# LCD.net
KiCad netlist of a schematic drawn in Altium Designer
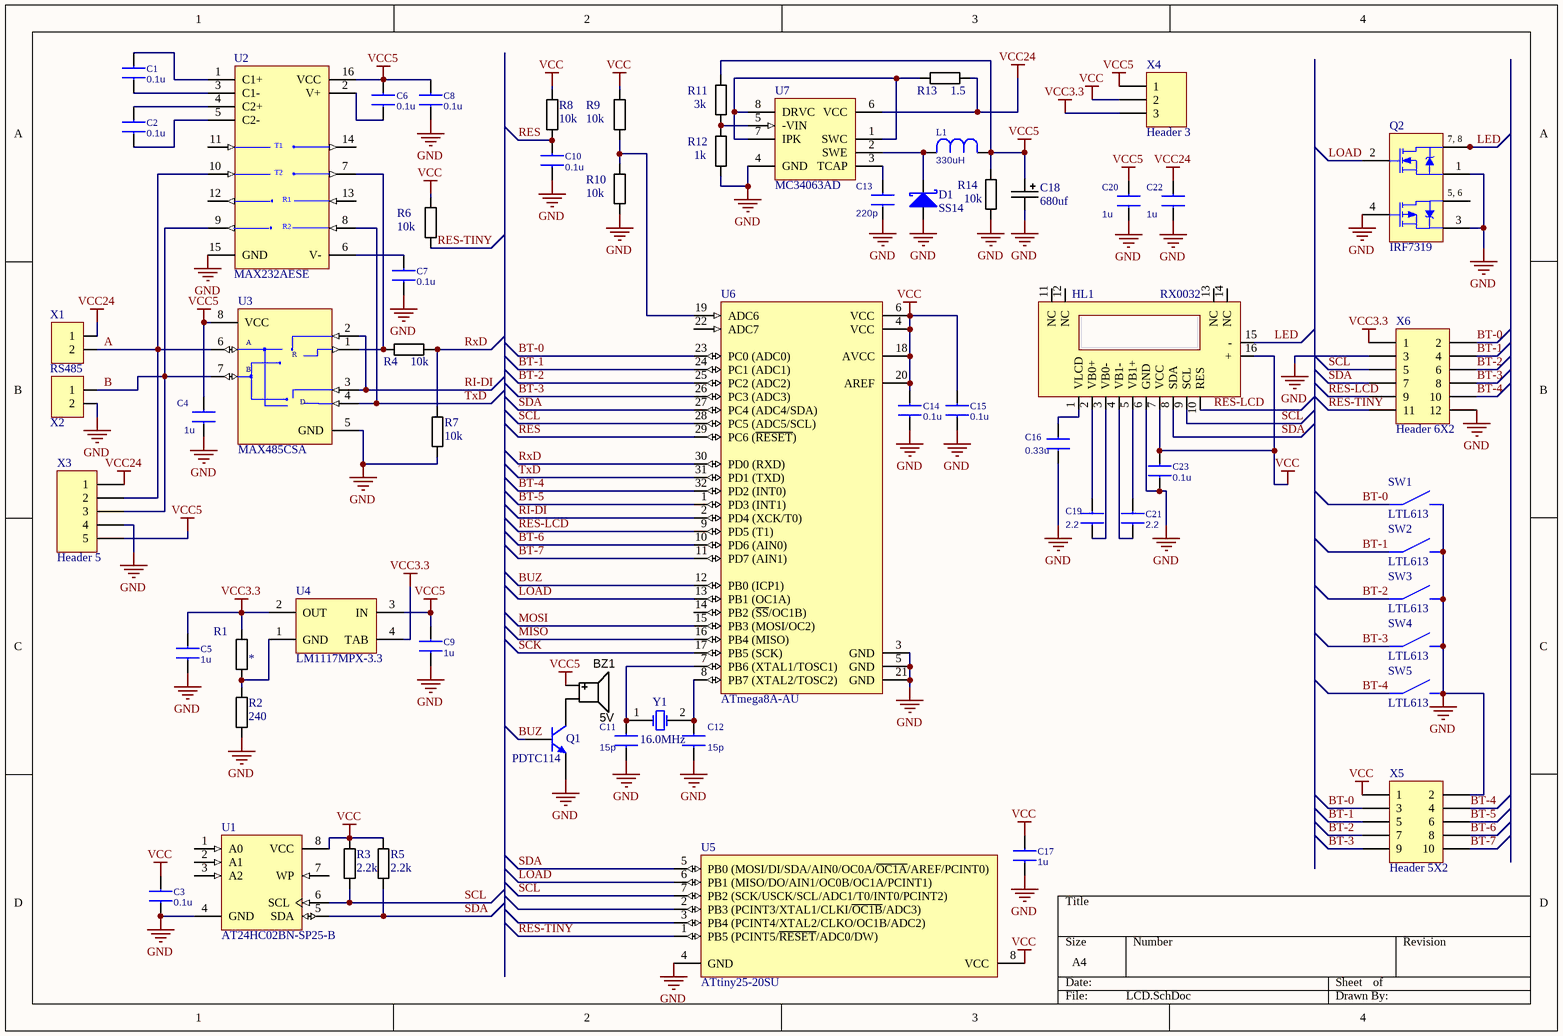
[diagram p0: LCD.SchDoc]

(export (version "E")
  (design (tool "Eeschema 10.0.6"))
  (components
    (comp (ref "BZ1")
      (value "Alternate part: 3100-932")
      (footprint "PBL - THD Packages:BUZZER_12.0X8.5MM")
      (description "Speaker, Magnetic Transducer")
      (fields (field (name "MANUFACTURER PART NUMBER 1") "5V"))
      (libsource (lib "PBL - Electromechanical") (part "BZ_12x8.5x6.5_2kHz"))
    )
    (comp (ref "C1")
      (value "0.1u")
      (footprint "C_0805")
      (description "Capacitor")
      (libsource (lib "AX_Altium_v2.3") (part "C0805"))
    )
    (comp (ref "C2")
      (value "0.1u")
      (footprint "C_0805")
      (description "Capacitor")
      (libsource (lib "AX_Altium_v2.3") (part "C0805"))
    )
    (comp (ref "C3")
      (value "0.1u")
      (footprint "C_0805")
      (description "Capacitor")
      (libsource (lib "AX_Altium_v2.3") (part "C0805"))
    )
    (comp (ref "C4")
      (value "1u")
      (footprint "C_0805")
      (description "Capacitor")
      (libsource (lib "AX_Altium_v2.3") (part "C0805"))
    )
    (comp (ref "C5")
      (value "1u")
      (footprint "C_0805")
      (description "Capacitor")
      (libsource (lib "AX_Altium_v2.3") (part "C0805"))
    )
    (comp (ref "C6")
      (value "0.1u")
      (footprint "C_0805")
      (description "Capacitor")
      (libsource (lib "AX_Altium_v2.3") (part "C0805"))
    )
    (comp (ref "C7")
      (value "0.1u")
      (footprint "C_0805")
      (description "Capacitor")
      (libsource (lib "AX_Altium_v2.3") (part "C0805"))
    )
    (comp (ref "C8")
      (value "0.1u")
      (footprint "C_0805")
      (description "Capacitor")
      (libsource (lib "AX_Altium_v2.3") (part "C0805"))
    )
    (comp (ref "C9")
      (value "1u")
      (footprint "C_0805")
      (description "Capacitor")
      (libsource (lib "AX_Altium_v2.3") (part "C0805"))
    )
    (comp (ref "C10")
      (value "0.1u")
      (footprint "C_0805")
      (description "Capacitor")
      (libsource (lib "AX_Altium_v2.3") (part "C0805"))
    )
    (comp (ref "C11")
      (value "15p")
      (footprint "C_0603")
      (description "Capacitor")
      (libsource (lib "AX_Altium_v2.3") (part "C0603"))
    )
    (comp (ref "C12")
      (value "15p")
      (footprint "C_0603")
      (description "Capacitor")
      (libsource (lib "AX_Altium_v2.3") (part "C0603"))
    )
    (comp (ref "C13")
      (value "220p")
      (footprint "C_0805")
      (description "Capacitor")
      (libsource (lib "AX_Altium_v2.3") (part "C0805"))
    )
    (comp (ref "C14")
      (value "0.1u")
      (footprint "C_0805")
      (description "Capacitor")
      (libsource (lib "AX_Altium_v2.3") (part "C0805"))
    )
    (comp (ref "C15")
      (value "0.1u")
      (footprint "C_0805")
      (description "Capacitor")
      (libsource (lib "AX_Altium_v2.3") (part "C0805"))
    )
    (comp (ref "C16")
      (value "0.33u")
      (footprint "C_0805")
      (description "Capacitor")
      (libsource (lib "AX_Altium_v2.3") (part "C0805"))
    )
    (comp (ref "C17")
      (value "1u")
      (footprint "C_0805")
      (description "Capacitor")
      (libsource (lib "AX_Altium_v2.3") (part "C0805"))
    )
    (comp (ref "C18")
      (value "680uf")
      (footprint "Cap-Elec-8x9pcb:PCBComponent_1")
      (fields (field (name "Comment") "Component_1"))
      (libsource (lib "Cap-Elec-8x9") (part "Component_1"))
    )
    (comp (ref "C19")
      (value "2.2")
      (footprint "C_1206")
      (description "Capacitor")
      (libsource (lib "AX_Altium_v2.3") (part "C1206"))
    )
    (comp (ref "C20")
      (value "1u")
      (footprint "C_0805")
      (description "Capacitor")
      (libsource (lib "AX_Altium_v2.3") (part "C0805"))
    )
    (comp (ref "C21")
      (value "2.2")
      (footprint "C_1206")
      (description "Capacitor")
      (libsource (lib "AX_Altium_v2.3") (part "C1206"))
    )
    (comp (ref "C22")
      (value "1u")
      (footprint "C_0805")
      (description "Capacitor")
      (libsource (lib "AX_Altium_v2.3") (part "C0805"))
    )
    (comp (ref "C23")
      (value "0.1u")
      (footprint "C_0805")
      (description "Capacitor")
      (libsource (lib "AX_Altium_v2.3") (part "C0805"))
    )
    (comp (ref "D1")
      (value "SS14")
      (footprint "DO-214AC")
      (description "Schottky Diode")
      (libsource (lib "AX_Altium_v2.3") (part "DS_DO-214"))
    )
    (comp (ref "HL1") (value "RX0032") (footprint "RX0032") (libsource (lib "RX0032") (part "RX0032")))
    (comp (ref "L1")
      (value "330uH")
      (footprint "CDRH74")
      (description "Inductor")
      (libsource (lib "AX_Altium_v2.3") (part "L_CDRH74"))
    )
    (comp (ref "Q1")
      (value "PDTC114")
      (footprint "SOT-23B_N")
      (description "NPN Bipolar Transistor")
      (fields (field (name "PUBLISHER") "Altium Limited"))
      (libsource (lib "Miscellaneous Devices") (part "QNPN"))
    )
    (comp (ref "Q2")
      (value "IRF7319")
      (footprint "SO-8")
      (description "HEXFET Power MOSFET")
      (fields (field (name "PUBLISHER") "Altium Limited"))
      (libsource (lib "AX_Altium_v2.3") (part "IRF7319"))
    )
    (comp (ref "R1") (value "*") (footprint "Resistor 0805") (libsource (lib "Maks_lib") (part "Resistor")))
    (comp (ref "R2") (value "240") (footprint "Resistor 0805") (libsource (lib "Maks_lib") (part "Resistor")))
    (comp (ref "R3")
      (value "2.2k")
      (footprint "Resistor 0603")
      (fields (field (name "Comment") "3k"))
      (libsource (lib "Maks_lib") (part "Resistor"))
    )
    (comp (ref "R4")
      (value "10k")
      (footprint "Resistor 0603")
      (fields (field (name "Comment") "3k"))
      (libsource (lib "Maks_lib") (part "Resistor"))
    )
    (comp (ref "R5")
      (value "2.2k")
      (footprint "Resistor 0603")
      (fields (field (name "Comment") "3k"))
      (libsource (lib "Maks_lib") (part "Resistor"))
    )
    (comp (ref "R6")
      (value "10k")
      (footprint "Resistor 0603")
      (fields (field (name "Comment") "3k"))
      (libsource (lib "Maks_lib") (part "Resistor"))
    )
    (comp (ref "R7")
      (value "10k")
      (footprint "Resistor 0603")
      (fields (field (name "Comment") "3k"))
      (libsource (lib "Maks_lib") (part "Resistor"))
    )
    (comp (ref "R8")
      (value "10k")
      (footprint "Resistor 0603")
      (fields (field (name "Comment") "3k"))
      (libsource (lib "Maks_lib") (part "Resistor"))
    )
    (comp (ref "R9")
      (value "10k")
      (footprint "Resistor 0603")
      (fields (field (name "Comment") "3k"))
      (libsource (lib "Maks_lib") (part "Resistor"))
    )
    (comp (ref "R10")
      (value "10k")
      (footprint "Resistor 0603")
      (fields (field (name "Comment") "3k"))
      (libsource (lib "Maks_lib") (part "Resistor"))
    )
    (comp (ref "R11") (value "3k") (footprint "Resistor 0603") (libsource (lib "Maks_lib") (part "Resistor")))
    (comp (ref "R12") (value "1k") (footprint "Resistor 0603") (libsource (lib "Maks_lib") (part "Resistor")))
    (comp (ref "R13")
      (value "1.5")
      (footprint "Resistor 1206")
      (fields (field (name "Comment") "3k"))
      (libsource (lib "Maks_lib") (part "Resistor"))
    )
    (comp (ref "R14")
      (value "10k")
      (footprint "Resistor 0603")
      (fields (field (name "Comment") "3k"))
      (libsource (lib "Maks_lib") (part "Resistor"))
    )
    (comp (ref "SW1")
      (value "LTL613")
      (footprint "LTL613")
      (description "Tact button switch")
      (libsource (lib "AX_Altium_v2.3") (part "Button_tact"))
    )
    (comp (ref "SW2")
      (value "LTL613")
      (footprint "LTL613")
      (description "Tact button switch")
      (libsource (lib "AX_Altium_v2.3") (part "Button_tact"))
    )
    (comp (ref "SW3")
      (value "LTL613")
      (footprint "LTL613")
      (description "Tact button switch")
      (libsource (lib "AX_Altium_v2.3") (part "Button_tact"))
    )
    (comp (ref "SW4")
      (value "LTL613")
      (footprint "LTL613")
      (description "Tact button switch")
      (libsource (lib "AX_Altium_v2.3") (part "Button_tact"))
    )
    (comp (ref "SW5")
      (value "LTL613")
      (footprint "LTL613")
      (description "Tact button switch")
      (libsource (lib "AX_Altium_v2.3") (part "Button_tact"))
    )
    (comp (ref "U1")
      (value "AT24HC02BN-SP25-B")
      (footprint "8S1_N")
      (fields (field (name "PUBLISHER") "Altium Limited"))
      (libsource (lib "Atmel Memory Serial EEPROM") (part "AT24HC02BN-SP25-B"))
    )
    (comp (ref "U2")
      (value "MAX232AESE")
      (footprint "NSO16_N")
      (description "+5V-Powered, Multichannel RS-232 Driver/Receiver")
      (fields (field (name "PUBLISHER") "Altium Limited"))
      (libsource (lib "Maxim Communication Transceiver") (part "MAX232AESE"))
    )
    (comp (ref "U3")
      (value "MAX485CSA")
      (footprint "NSO8_N")
      (description "Low-Power, Slew-Rate-Limited RS-485/RS-422 Transceiver")
      (fields (field (name "PUBLISHER") "Altium Limited"))
      (libsource (lib "Maxim Communication Transceiver") (part "MAX485CSA"))
    )
    (comp (ref "U4")
      (value "LM1117MPX-3.3")
      (footprint "MP04A_N")
      (description "800mA Low-Dropout Linear Regulator, 4-pin SOT-223")
      (fields
        (field (name "MANUFACTURER") "National Semiconductor")
        (field (name "PUBLISHER") "Altium Limited")
      )
      (libsource (lib "NSC LDO") (part "LM1117MPX-3.3"))
    )
    (comp (ref "U5")
      (value "ATtiny25-20SU")
      (footprint "8S2_N")
      (fields (field (name "PUBLISHER") "Altium Limited"))
      (libsource (lib "Atmel Microcontroller 8-Bit tinyAVR") (part "ATtiny25-20SU"))
    )
    (comp (ref "U6")
      (value "ATmega8A-AU")
      (footprint "32A_N")
      (fields (field (name "PUBLISHER") "Altium Limited"))
      (libsource (lib "Atmel Microcontroller 8-Bit megaAVR") (part "ATmega8A-AU"))
    )
    (comp (ref "U7")
      (value "MC34063AD")
      (footprint "751-02_N")
      (description "DC-to-DC Converter Control Circuit")
      (fields (field (name "PUBLISHER") "Altium Limited"))
      (libsource (lib "Motorola Power Mgt DC-DC Converter") (part "MC34063AD"))
    )
    (comp (ref "X1")
      (value "DG-2P-35")
      (footprint "DG-2P-35")
      (libsource (lib "Degson-uni-2P-35") (part "DG-2P-35"))
    )
    (comp (ref "X2")
      (value "DG-2P-35")
      (footprint "DG-2P-35")
      (fields (field (name "FOR") "RS485"))
      (libsource (lib "Degson-uni-2P-35") (part "DG-2P-35"))
    )
    (comp (ref "X3")
      (value "Header 5")
      (footprint "HDR1X5")
      (description "Header, 5-Pin")
      (fields (field (name "PUBLISHER") "Altium Limited"))
      (libsource (lib "Miscellaneous Connectors") (part "Header 5"))
    )
    (comp (ref "X4")
      (value "Header 3")
      (footprint "HDR1X3")
      (description "Header, 3-Pin")
      (fields (field (name "PUBLISHER") "Altium Limited"))
      (libsource (lib "Miscellaneous Connectors") (part "Header 3"))
    )
    (comp (ref "X5")
      (value "Header 5X2")
      (footprint "HDR2X5")
      (description "Header, 5-Pin, Dual row")
      (fields (field (name "PUBLISHER") "Altium Limited"))
      (libsource (lib "Miscellaneous Connectors") (part "Header 5X2"))
    )
    (comp (ref "X6")
      (value "Header 6X2")
      (footprint "HDR2X6")
      (description "Header, 6-Pin, Dual row")
      (fields (field (name "PUBLISHER") "Altium Limited"))
      (libsource (lib "Miscellaneous Connectors") (part "Header 6X2"))
    )
    (comp (ref "Y1")
      (value "16.0MHz")
      (footprint "HC49/4H_SMX")
      (description "Surface Mount Quartz Crystal")
      (fields (field (name "Comment") "HC49/4H_SMX") (field (name "PUBLISHER") "Altium Limited"))
      (libsource (lib "C-MAC Crystal Oscillator") (part "HC49/4H_SMX"))
    )
  )
  (nets
    (net (code "1") (name "/A") (class "Default")
      (node (ref "U2") (pin "10") (pinfunction "T2IN_10") (pintype "input"))
      (node (ref "U3") (pin "6") (pinfunction "A_6") (pintype "bidirectional"))
      (node (ref "X1") (pin "2") (pinfunction "2_2") (pintype "passive"))
      (node (ref "X3") (pin "2") (pinfunction "2_2") (pintype "passive"))
    )
    (net (code "2") (name "/B") (class "Default")
      (node (ref "U2") (pin "9") (pinfunction "R2OUT_9") (pintype "output"))
      (node (ref "U3") (pin "7") (pinfunction "B_7") (pintype "bidirectional"))
      (node (ref "X2") (pin "1") (pinfunction "1_1") (pintype "passive"))
      (node (ref "X3") (pin "3") (pinfunction "3_3") (pintype "passive"))
    )
    (net (code "3") (name "/BT-0") (class "Default")
      (node (ref "SW1") (pin "0") (pinfunction "0_0") (pintype "passive"))
      (node (ref "U6") (pin "23") (pinfunction "PC0_(ADC0)_23") (pintype "bidirectional"))
      (node (ref "X5") (pin "3") (pinfunction "3_3") (pintype "passive"))
      (node (ref "X6") (pin "2") (pinfunction "2_2") (pintype "passive"))
    )
    (net (code "4") (name "/BT-1") (class "Default")
      (node (ref "SW2") (pin "0") (pinfunction "0_0") (pintype "passive"))
      (node (ref "U6") (pin "24") (pinfunction "PC1_(ADC1)_24") (pintype "bidirectional"))
      (node (ref "X5") (pin "5") (pinfunction "5_5") (pintype "passive"))
      (node (ref "X6") (pin "4") (pinfunction "4_4") (pintype "passive"))
    )
    (net (code "5") (name "/BT-2") (class "Default")
      (node (ref "SW3") (pin "0") (pinfunction "0_0") (pintype "passive"))
      (node (ref "U6") (pin "25") (pinfunction "PC2_(ADC2)_25") (pintype "bidirectional"))
      (node (ref "X5") (pin "7") (pinfunction "7_7") (pintype "passive"))
      (node (ref "X6") (pin "6") (pinfunction "6_6") (pintype "passive"))
    )
    (net (code "6") (name "/BT-3") (class "Default")
      (node (ref "SW4") (pin "0") (pinfunction "0_0") (pintype "passive"))
      (node (ref "U6") (pin "26") (pinfunction "PC3_(ADC3)_26") (pintype "bidirectional"))
      (node (ref "X5") (pin "9") (pinfunction "9_9") (pintype "passive"))
      (node (ref "X6") (pin "8") (pinfunction "8_8") (pintype "passive"))
    )
    (net (code "7") (name "/BT-4") (class "Default")
      (node (ref "SW5") (pin "0") (pinfunction "0_0") (pintype "passive"))
      (node (ref "U6") (pin "32") (pinfunction "PD2_(INT0)_32") (pintype "bidirectional"))
      (node (ref "X5") (pin "4") (pinfunction "4_4") (pintype "passive"))
      (node (ref "X6") (pin "10") (pinfunction "10_10") (pintype "passive"))
    )
    (net (code "8") (name "/BT-5") (class "Default")
      (node (ref "U6") (pin "1") (pinfunction "PD3_(INT1)_1") (pintype "bidirectional"))
      (node (ref "X5") (pin "6") (pinfunction "6_6") (pintype "passive"))
    )
    (net (code "9") (name "/BT-6") (class "Default")
      (node (ref "U6") (pin "10") (pinfunction "PD6_(AIN0)_10") (pintype "bidirectional"))
      (node (ref "X5") (pin "8") (pinfunction "8_8") (pintype "passive"))
    )
    (net (code "10") (name "/BT-7") (class "Default")
      (node (ref "U6") (pin "11") (pinfunction "PD7_(AIN1)_11") (pintype "bidirectional"))
      (node (ref "X5") (pin "10") (pinfunction "10_10") (pintype "passive"))
    )
    (net (code "11") (name "/BUZ") (class "Default")
      (node (ref "Q1") (pin "2") (pinfunction "B_2") (pintype "passive"))
      (node (ref "U6") (pin "12") (pinfunction "PB0_(ICP1)_12") (pintype "bidirectional"))
    )
    (net (code "12") (name "/LED") (class "Default")
      (node (ref "HL1") (pin "15") (pinfunction "-_15") (pintype "passive"))
      (node (ref "Q2") (pin "7") (pinfunction "D1_7") (pintype "passive"))
      (node (ref "Q2") (pin "8") (pinfunction "D1_8") (pintype "passive"))
    )
    (net (code "13") (name "/LOAD") (class "Default")
      (node (ref "Q2") (pin "2") (pinfunction "G1_2") (pintype "passive"))
      (node (ref "U5") (pin "6") (pinfunction "PB1_(MISO/DO/AIN1/OC0B/OC1A/PCINT1)_6") (pintype "bidirectional"))
      (node (ref "U6") (pin "13") (pinfunction "PB1_(OC1A)_13") (pintype "bidirectional"))
    )
    (net (code "14") (name "/MISO") (class "Default")
      (node (ref "U6") (pin "16") (pinfunction "PB4_(MISO)_16") (pintype "bidirectional"))
    )
    (net (code "15") (name "/MOSI") (class "Default")
      (node (ref "U6") (pin "15") (pinfunction "PB3_(MOSI/OC2)_15") (pintype "bidirectional"))
    )
    (net (code "16") (name "/RES") (class "Default")
      (node (ref "C10") (pin "2") (pintype "passive"))
      (node (ref "R8") (pin "1") (pinfunction "1_1") (pintype "passive"))
      (node (ref "U6") (pin "29") (pinfunction "PC6_(~{RESET})_29") (pintype "bidirectional"))
    )
    (net (code "17") (name "/RES-LCD") (class "Default")
      (node (ref "HL1") (pin "10") (pinfunction "RES_10") (pintype "passive"))
      (node (ref "U6") (pin "9") (pinfunction "PD5_(T1)_9") (pintype "bidirectional"))
      (node (ref "X6") (pin "9") (pinfunction "9_9") (pintype "passive"))
    )
    (net (code "18") (name "/RES-TINY") (class "Default")
      (node (ref "R6") (pin "1") (pinfunction "1_1") (pintype "passive"))
      (node (ref "U5") (pin "1") (pinfunction "PB5_(PCINT5/~{RESET}/ADC0/DW)_1") (pintype "bidirectional"))
      (node (ref "X6") (pin "11") (pinfunction "11_11") (pintype "passive"))
    )
    (net (code "19") (name "/RI-DI") (class "Default")
      (node (ref "U3") (pin "2") (pinfunction "~{RE}_2") (pintype "input"))
      (node (ref "U3") (pin "3") (pinfunction "DE_3") (pintype "input"))
      (node (ref "U6") (pin "2") (pinfunction "PD4_(XCK/T0)_2") (pintype "bidirectional"))
    )
    (net (code "20") (name "/RxD") (class "Default")
      (node (ref "R4") (pin "1") (pinfunction "1_1") (pintype "passive"))
      (node (ref "R7") (pin "2") (pinfunction "2_2") (pintype "passive"))
      (node (ref "U6") (pin "30") (pinfunction "PD0_(RXD)_30") (pintype "bidirectional"))
    )
    (net (code "21") (name "/SCK") (class "Default")
      (node (ref "U6") (pin "17") (pinfunction "PB5_(SCK)_17") (pintype "bidirectional"))
    )
    (net (code "22") (name "/SCL") (class "Default")
      (node (ref "HL1") (pin "9") (pinfunction "SCL_9") (pintype "passive"))
      (node (ref "R3") (pin "1") (pinfunction "1_1") (pintype "passive"))
      (node (ref "U1") (pin "6") (pinfunction "SCL_6") (pintype "input"))
      (node (ref "U5") (pin "7") (pinfunction "PB2_(SCK/USCK/SCL/ADC1/T0/INT0/PCINT2)_7") (pintype "bidirectional"))
      (node (ref "U6") (pin "28") (pinfunction "PC5_(ADC5/SCL)_28") (pintype "bidirectional"))
      (node (ref "X6") (pin "5") (pinfunction "5_5") (pintype "passive"))
    )
    (net (code "23") (name "/SDA") (class "Default")
      (node (ref "HL1") (pin "8") (pinfunction "SDA_8") (pintype "passive"))
      (node (ref "R5") (pin "1") (pinfunction "1_1") (pintype "passive"))
      (node (ref "U1") (pin "5") (pinfunction "SDA_5") (pintype "bidirectional"))
      (node (ref "U5") (pin "5") (pinfunction "PB0_(MOSI/DI/SDA/AIN0/OC0A/~{OC1A}/AREF/PCINT0)_5") (pintype "bidirectional"))
      (node (ref "U6") (pin "27") (pinfunction "PC4_(ADC4/SDA)_27") (pintype "bidirectional"))
      (node (ref "X6") (pin "7") (pinfunction "7_7") (pintype "passive"))
    )
    (net (code "24") (name "/TxD") (class "Default")
      (node (ref "U2") (pin "8") (pinfunction "R2IN_8") (pintype "input"))
      (node (ref "U3") (pin "4") (pinfunction "DI_4") (pintype "input"))
      (node (ref "U6") (pin "31") (pinfunction "PD1_(TXD)_31") (pintype "bidirectional"))
    )
    (net (code "25") (name "GND") (class "Default")
      (node (ref "C10") (pin "1") (pintype "passive"))
      (node (ref "C11") (pin "1") (pintype "passive"))
      (node (ref "C12") (pin "1") (pintype "passive"))
      (node (ref "C13") (pin "1") (pintype "passive"))
      (node (ref "C14") (pin "1") (pintype "passive"))
      (node (ref "C15") (pin "1") (pintype "passive"))
      (node (ref "C16") (pin "1") (pintype "passive"))
      (node (ref "C17") (pin "2") (pintype "passive"))
      (node (ref "C18") (pin "2") (pinfunction "2_2") (pintype "passive"))
      (node (ref "C20") (pin "1") (pintype "passive"))
      (node (ref "C22") (pin "1") (pintype "passive"))
      (node (ref "C23") (pin "1") (pintype "passive"))
      (node (ref "C3") (pin "1") (pintype "passive"))
      (node (ref "C4") (pin "1") (pintype "passive"))
      (node (ref "C5") (pin "1") (pintype "passive"))
      (node (ref "C7") (pin "1") (pintype "passive"))
      (node (ref "C8") (pin "1") (pintype "passive"))
      (node (ref "C9") (pin "1") (pintype "passive"))
      (node (ref "D1") (pin "1") (pinfunction "A_1") (pintype "passive"))
      (node (ref "HL1") (pin "6") (pinfunction "GND_6") (pintype "passive"))
      (node (ref "Q1") (pin "3") (pinfunction "E_3") (pintype "passive"))
      (node (ref "Q2") (pin "1") (pinfunction "S1_1") (pintype "passive"))
      (node (ref "Q2") (pin "3") (pinfunction "S2_3") (pintype "passive"))
      (node (ref "Q2") (pin "4") (pinfunction "G2_4") (pintype "passive"))
      (node (ref "R10") (pin "1") (pinfunction "1_1") (pintype "passive"))
      (node (ref "R12") (pin "1") (pinfunction "1_1") (pintype "passive"))
      (node (ref "R14") (pin "1") (pinfunction "1_1") (pintype "passive"))
      (node (ref "R2") (pin "1") (pinfunction "1_1") (pintype "passive"))
      (node (ref "R7") (pin "1") (pinfunction "1_1") (pintype "passive"))
      (node (ref "SW1") (pin "1") (pinfunction "1_1") (pintype "passive"))
      (node (ref "SW2") (pin "1") (pinfunction "1_1") (pintype "passive"))
      (node (ref "SW3") (pin "1") (pinfunction "1_1") (pintype "passive"))
      (node (ref "SW4") (pin "1") (pinfunction "1_1") (pintype "passive"))
      (node (ref "SW5") (pin "1") (pinfunction "1_1") (pintype "passive"))
      (node (ref "U1") (pin "4") (pinfunction "GND_4") (pintype "power_in"))
      (node (ref "U2") (pin "15") (pinfunction "GND_15") (pintype "power_in"))
      (node (ref "U3") (pin "5") (pinfunction "GND_5") (pintype "power_in"))
      (node (ref "U5") (pin "4") (pinfunction "GND_4") (pintype "power_in"))
      (node (ref "U6") (pin "21") (pinfunction "GND_21") (pintype "power_in"))
      (node (ref "U6") (pin "3") (pinfunction "GND_3") (pintype "power_in"))
      (node (ref "U6") (pin "5") (pinfunction "GND_5") (pintype "power_in"))
      (node (ref "U7") (pin "4") (pinfunction "GND_4") (pintype "power_in"))
      (node (ref "X2") (pin "2") (pinfunction "2_2") (pintype "passive"))
      (node (ref "X3") (pin "4") (pinfunction "4_4") (pintype "passive"))
      (node (ref "X5") (pin "2") (pinfunction "2_2") (pintype "passive"))
      (node (ref "X6") (pin "12") (pinfunction "12_12") (pintype "passive"))
      (node (ref "X6") (pin "3") (pinfunction "3_3") (pintype "passive"))
    )
    (net (code "26") (name "Net-(BZ1-Negative)") (class "Default")
      (node (ref "BZ1") (pin "2") (pinfunction "Negative_2") (pintype "passive"))
      (node (ref "Q1") (pin "1") (pinfunction "C_1") (pintype "passive"))
    )
    (net (code "27") (name "Net-(D1-K)") (class "Default")
      (node (ref "D1") (pin "2") (pinfunction "K_2") (pintype "passive"))
      (node (ref "L1") (pin "2") (pintype "passive"))
      (node (ref "U7") (pin "2") (pinfunction "SWE_2") (pintype "open_emitter"))
    )
    (net (code "28") (name "Net-(HL1-VB0+)") (class "Default")
      (node (ref "C19") (pin "2") (pintype "passive"))
      (node (ref "HL1") (pin "2") (pinfunction "VB0+_2") (pintype "passive"))
    )
    (net (code "29") (name "Net-(HL1-VB0-)") (class "Default")
      (node (ref "C19") (pin "1") (pintype "passive"))
      (node (ref "HL1") (pin "3") (pinfunction "VB0-_3") (pintype "passive"))
    )
    (net (code "30") (name "Net-(HL1-VB1+)") (class "Default")
      (node (ref "C21") (pin "2") (pintype "passive"))
      (node (ref "HL1") (pin "5") (pinfunction "VB1+_5") (pintype "passive"))
    )
    (net (code "31") (name "Net-(HL1-VB1-)") (class "Default")
      (node (ref "C21") (pin "1") (pintype "passive"))
      (node (ref "HL1") (pin "4") (pinfunction "VB1-_4") (pintype "passive"))
    )
    (net (code "32") (name "Net-(HL1-VLCD)") (class "Default")
      (node (ref "C16") (pin "2") (pintype "passive"))
      (node (ref "HL1") (pin "1") (pinfunction "VLCD_1") (pintype "passive"))
    )
    (net (code "33") (name "Net-(Q2-D2-Pad5)") (class "Default")
      (node (ref "Q2") (pin "5") (pinfunction "D2_5") (pintype "passive"))
      (node (ref "Q2") (pin "6") (pinfunction "D2_6") (pintype "passive"))
    )
    (net (code "34") (name "Net-(U2-C1+)") (class "Default")
      (node (ref "C1") (pin "2") (pintype "passive"))
      (node (ref "U2") (pin "1") (pinfunction "C1+_1") (pintype "passive"))
    )
    (net (code "35") (name "Net-(U2-C1-)") (class "Default")
      (node (ref "C1") (pin "1") (pintype "passive"))
      (node (ref "U2") (pin "3") (pinfunction "C1-_3") (pintype "passive"))
    )
    (net (code "36") (name "Net-(U2-C2+)") (class "Default")
      (node (ref "C2") (pin "2") (pintype "passive"))
      (node (ref "U2") (pin "4") (pinfunction "C2+_4") (pintype "passive"))
    )
    (net (code "37") (name "Net-(U2-C2-)") (class "Default")
      (node (ref "C2") (pin "1") (pintype "passive"))
      (node (ref "U2") (pin "5") (pinfunction "C2-_5") (pintype "passive"))
    )
    (net (code "38") (name "Net-(U2-T2OUT)") (class "Default")
      (node (ref "R4") (pin "2") (pinfunction "2_2") (pintype "passive"))
      (node (ref "U2") (pin "7") (pinfunction "T2OUT_7") (pintype "output"))
      (node (ref "U3") (pin "1") (pinfunction "RO_1") (pintype "output"))
    )
    (net (code "39") (name "Net-(U2-V+)") (class "Default")
      (node (ref "C6") (pin "1") (pintype "passive"))
      (node (ref "U2") (pin "2") (pinfunction "V+_2") (pintype "power_in"))
    )
    (net (code "40") (name "Net-(U2-V-)") (class "Default")
      (node (ref "C7") (pin "2") (pintype "passive"))
      (node (ref "U2") (pin "6") (pinfunction "V-_6") (pintype "power_in"))
    )
    (net (code "41") (name "Net-(U4-GND)") (class "Default")
      (node (ref "R1") (pin "1") (pinfunction "1_1") (pintype "passive"))
      (node (ref "R2") (pin "2") (pinfunction "2_2") (pintype "passive"))
      (node (ref "U4") (pin "1") (pinfunction "GND_1") (pintype "power_in"))
    )
    (net (code "42") (name "Net-(U6-ADC6)") (class "Default")
      (node (ref "R10") (pin "2") (pinfunction "2_2") (pintype "passive"))
      (node (ref "R9") (pin "1") (pinfunction "1_1") (pintype "passive"))
      (node (ref "U6") (pin "19") (pinfunction "ADC6_19") (pintype "input"))
    )
    (net (code "43") (name "Net-(U6-PB6_(XTAL1{slash}TOSC1))") (class "Default")
      (node (ref "C11") (pin "2") (pintype "passive"))
      (node (ref "U6") (pin "7") (pinfunction "PB6_(XTAL1/TOSC1)_7") (pintype "bidirectional"))
      (node (ref "Y1") (pin "1") (pinfunction "OSC1_1") (pintype "passive"))
    )
    (net (code "44") (name "Net-(U6-PB7_(XTAL2{slash}TOSC2))") (class "Default")
      (node (ref "C12") (pin "2") (pintype "passive"))
      (node (ref "U6") (pin "8") (pinfunction "PB7_(XTAL2/TOSC2)_8") (pintype "bidirectional"))
      (node (ref "Y1") (pin "2") (pinfunction "OSC2_2") (pintype "passive"))
    )
    (net (code "45") (name "Net-(U7--VIN)") (class "Default")
      (node (ref "R11") (pin "2") (pinfunction "2_2") (pintype "passive"))
      (node (ref "R12") (pin "2") (pinfunction "2_2") (pintype "passive"))
      (node (ref "U7") (pin "5") (pinfunction "-VIN_5") (pintype "input"))
    )
    (net (code "46") (name "Net-(U7-DRVC)") (class "Default")
      (node (ref "R13") (pin "2") (pinfunction "2_2") (pintype "passive"))
      (node (ref "U7") (pin "1") (pinfunction "SWC_1") (pintype "open_collector"))
      (node (ref "U7") (pin "7") (pinfunction "IPK_7") (pintype "passive"))
      (node (ref "U7") (pin "8") (pinfunction "DRVC_8") (pintype "open_collector"))
    )
    (net (code "47") (name "Net-(U7-TCAP)") (class "Default")
      (node (ref "C13") (pin "2") (pintype "passive"))
      (node (ref "U7") (pin "3") (pinfunction "TCAP_3") (pintype "passive"))
    )
    (net (code "48") (name "VCC") (class "Default")
      (node (ref "C14") (pin "2") (pintype "passive"))
      (node (ref "C15") (pin "2") (pintype "passive"))
      (node (ref "C17") (pin "1") (pintype "passive"))
      (node (ref "C23") (pin "2") (pintype "passive"))
      (node (ref "C3") (pin "2") (pintype "passive"))
      (node (ref "HL1") (pin "16") (pinfunction "+_16") (pintype "passive"))
      (node (ref "HL1") (pin "7") (pinfunction "VCC_7") (pintype "passive"))
      (node (ref "R3") (pin "2") (pinfunction "2_2") (pintype "passive"))
      (node (ref "R5") (pin "2") (pinfunction "2_2") (pintype "passive"))
      (node (ref "R6") (pin "2") (pinfunction "2_2") (pintype "passive"))
      (node (ref "R8") (pin "2") (pinfunction "2_2") (pintype "passive"))
      (node (ref "R9") (pin "2") (pinfunction "2_2") (pintype "passive"))
      (node (ref "U1") (pin "8") (pinfunction "VCC_8") (pintype "power_in"))
      (node (ref "U5") (pin "8") (pinfunction "VCC_8") (pintype "power_in"))
      (node (ref "U6") (pin "18") (pinfunction "AVCC_18") (pintype "power_in"))
      (node (ref "U6") (pin "20") (pinfunction "AREF_20") (pintype "power_in"))
      (node (ref "U6") (pin "4") (pinfunction "VCC_4") (pintype "power_in"))
      (node (ref "U6") (pin "6") (pinfunction "VCC_6") (pintype "power_in"))
      (node (ref "X4") (pin "2") (pinfunction "2_2") (pintype "passive"))
      (node (ref "X5") (pin "1") (pinfunction "1_1") (pintype "passive"))
    )
    (net (code "49") (name "VCC3.3") (class "Default")
      (node (ref "C5") (pin "2") (pintype "passive"))
      (node (ref "R1") (pin "2") (pinfunction "2_2") (pintype "passive"))
      (node (ref "U4") (pin "2") (pinfunction "OUT_2") (pintype "power_in"))
      (node (ref "U4") (pin "4") (pinfunction "TAB_4") (pintype "power_in"))
      (node (ref "X4") (pin "3") (pinfunction "3_3") (pintype "passive"))
      (node (ref "X6") (pin "1") (pinfunction "1_1") (pintype "passive"))
    )
    (net (code "50") (name "VCC5") (class "Default")
      (node (ref "BZ1") (pin "1") (pinfunction "Positive_1") (pintype "passive"))
      (node (ref "C18") (pin "1") (pinfunction "1_1") (pintype "passive"))
      (node (ref "C20") (pin "2") (pintype "passive"))
      (node (ref "C4") (pin "2") (pintype "passive"))
      (node (ref "C6") (pin "2") (pintype "passive"))
      (node (ref "C8") (pin "2") (pintype "passive"))
      (node (ref "C9") (pin "2") (pintype "passive"))
      (node (ref "L1") (pin "1") (pintype "passive"))
      (node (ref "R11") (pin "1") (pinfunction "1_1") (pintype "passive"))
      (node (ref "R14") (pin "2") (pinfunction "2_2") (pintype "passive"))
      (node (ref "U2") (pin "16") (pinfunction "VCC_16") (pintype "power_in"))
      (node (ref "U3") (pin "8") (pinfunction "VCC_8") (pintype "power_in"))
      (node (ref "U4") (pin "3") (pinfunction "IN_3") (pintype "power_in"))
      (node (ref "X3") (pin "5") (pinfunction "5_5") (pintype "passive"))
      (node (ref "X4") (pin "1") (pinfunction "1_1") (pintype "passive"))
    )
    (net (code "51") (name "VCC24") (class "Default")
      (node (ref "C22") (pin "2") (pintype "passive"))
      (node (ref "R13") (pin "1") (pinfunction "1_1") (pintype "passive"))
      (node (ref "U7") (pin "6") (pinfunction "VCC_6") (pintype "power_in"))
      (node (ref "X1") (pin "1") (pinfunction "1_1") (pintype "passive"))
      (node (ref "X3") (pin "1") (pinfunction "1_1") (pintype "passive"))
    )
    (net (code "52") (name "unconnected-(HL1-NC-Pad11)") (class "Default")
      (node (ref "HL1") (pin "11") (pinfunction "NC_11") (pintype "passive"))
    )
    (net (code "53") (name "unconnected-(HL1-NC-Pad12)") (class "Default")
      (node (ref "HL1") (pin "12") (pinfunction "NC_12") (pintype "passive"))
    )
    (net (code "54") (name "unconnected-(HL1-NC-Pad13)") (class "Default")
      (node (ref "HL1") (pin "13") (pinfunction "NC_13") (pintype "passive"))
    )
    (net (code "55") (name "unconnected-(HL1-NC-Pad14)") (class "Default")
      (node (ref "HL1") (pin "14") (pinfunction "NC_14") (pintype "passive"))
    )
    (net (code "56") (name "unconnected-(U1-A0-Pad1)") (class "Default")
      (node (ref "U1") (pin "1") (pinfunction "A0_1") (pintype "input"))
    )
    (net (code "57") (name "unconnected-(U1-A1-Pad2)") (class "Default")
      (node (ref "U1") (pin "2") (pinfunction "A1_2") (pintype "input"))
    )
    (net (code "58") (name "unconnected-(U1-A2-Pad3)") (class "Default")
      (node (ref "U1") (pin "3") (pinfunction "A2_3") (pintype "input"))
    )
    (net (code "59") (name "unconnected-(U1-WP-Pad7)") (class "Default")
      (node (ref "U1") (pin "7") (pinfunction "WP_7") (pintype "input"))
    )
    (net (code "60") (name "unconnected-(U2-R1IN-Pad13)") (class "Default")
      (node (ref "U2") (pin "13") (pinfunction "R1IN_13") (pintype "input"))
    )
    (net (code "61") (name "unconnected-(U2-R1OUT-Pad12)") (class "Default")
      (node (ref "U2") (pin "12") (pinfunction "R1OUT_12") (pintype "output"))
    )
    (net (code "62") (name "unconnected-(U2-T1IN-Pad11)") (class "Default")
      (node (ref "U2") (pin "11") (pinfunction "T1IN_11") (pintype "input"))
    )
    (net (code "63") (name "unconnected-(U2-T1OUT-Pad14)") (class "Default")
      (node (ref "U2") (pin "14") (pinfunction "T1OUT_14") (pintype "output"))
    )
    (net (code "64") (name "unconnected-(U5-PB3_(PCINT3{slash}XTAL1{slash}CLKI{slash}~{OC1B}{slash}ADC3)-Pad2)") (class "Default")
      (node (ref "U5") (pin "2") (pinfunction "PB3_(PCINT3/XTAL1/CLKI/~{OC1B}/ADC3)_2") (pintype "bidirectional"))
    )
    (net (code "65") (name "unconnected-(U5-PB4_(PCINT4{slash}XTAL2{slash}CLKO{slash}OC1B{slash}ADC2)-Pad3)") (class "Default")
      (node (ref "U5") (pin "3") (pinfunction "PB4_(PCINT4/XTAL2/CLKO/OC1B/ADC2)_3") (pintype "bidirectional"))
    )
    (net (code "66") (name "unconnected-(U6-ADC7-Pad22)") (class "Default")
      (node (ref "U6") (pin "22") (pinfunction "ADC7_22") (pintype "input"))
    )
    (net (code "67") (name "unconnected-(U6-PB2_(~{SS}{slash}OC1B)-Pad14)") (class "Default")
      (node (ref "U6") (pin "14") (pinfunction "PB2_(~{SS}/OC1B)_14") (pintype "bidirectional"))
    )
  )
)
